# COEX_PDB_schematics.net
KiCad netlist of a schematic drawn in Altium Designer
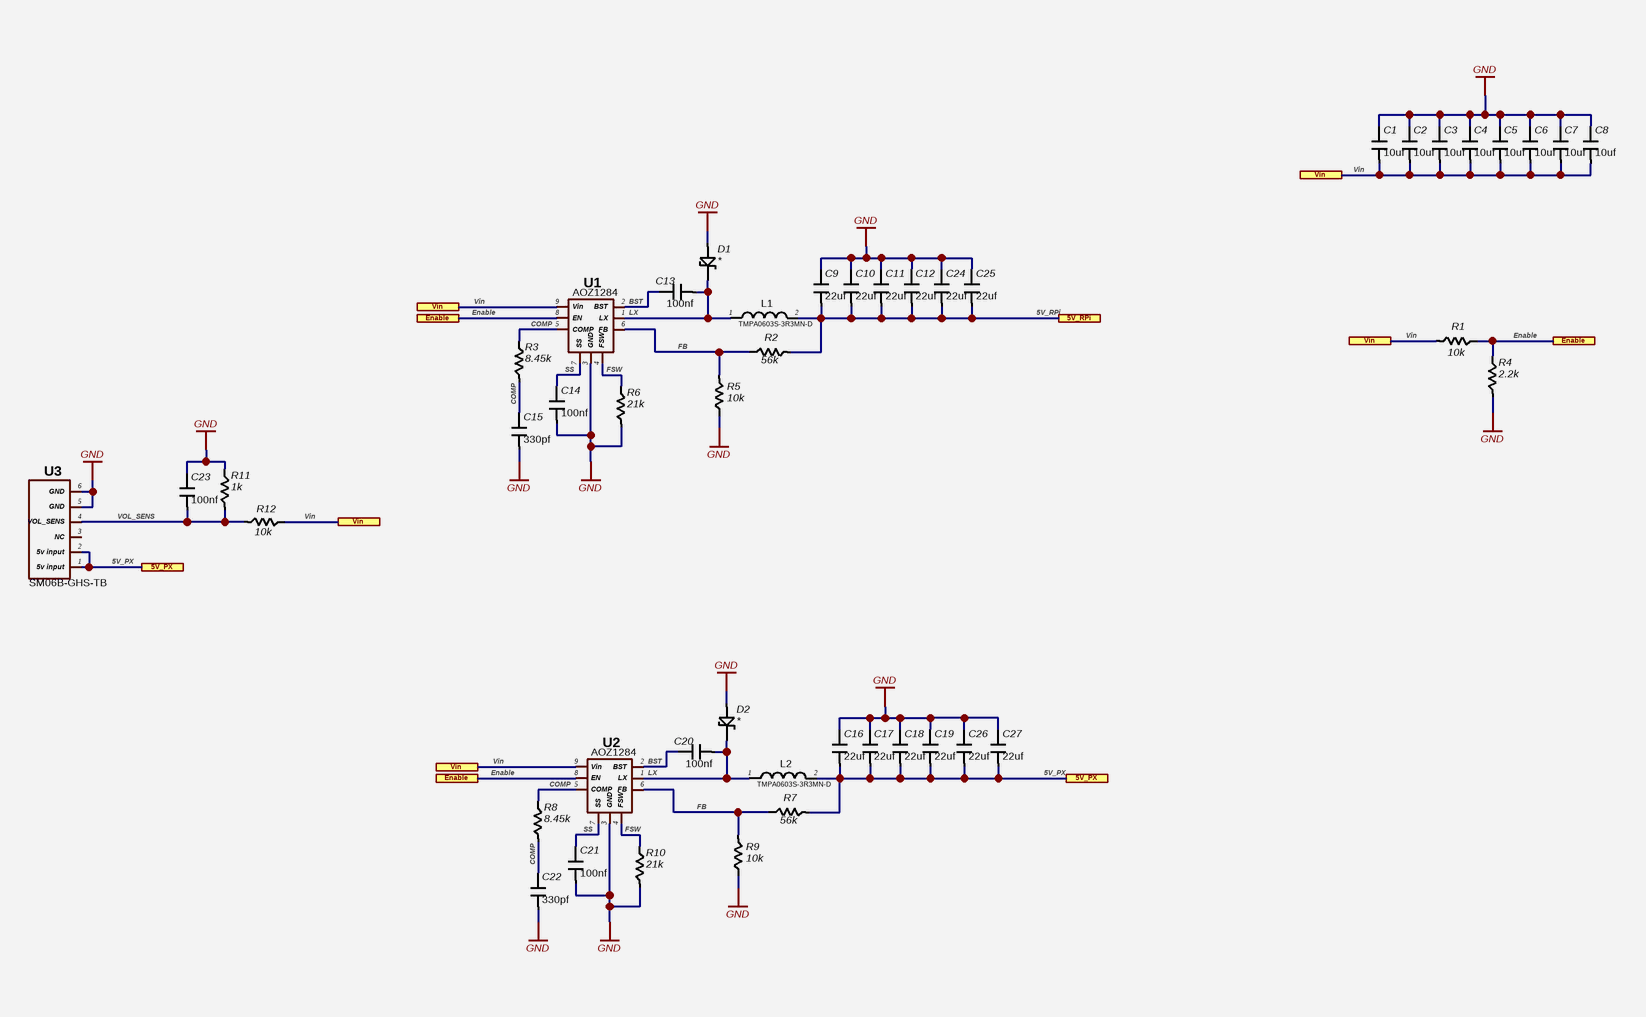
[diagram p0: COEX PDB schematics.SchDoc]

(export (version "E")
  (design (tool "Eeschema 10.0.6"))
  (components
    (comp (ref "C1")
      (value "10uf")
      (footprint "Capasitor 0805")
      (description "Multilayer Ceramic Capacitors MLCC - SMD/SMT 10uF 35V 0805")
      (fields
        (field (name "PART NUMBER") "GRM21BR6YA106KE43L")
        (field (name "MANUFACTURER") "Murata Electronics")
      )
      (libsource (lib "Schematic symbols library") (part "Capacitor MLCC"))
    )
    (comp (ref "C2")
      (value "10uf")
      (footprint "Capasitor 0805")
      (description "Multilayer Ceramic Capacitors MLCC - SMD/SMT 10uF 35V 0805")
      (fields
        (field (name "PART NUMBER") "GRM21BR6YA106KE43L")
        (field (name "MANUFACTURER") "Murata Electronics")
      )
      (libsource (lib "Schematic symbols library") (part "Capacitor MLCC"))
    )
    (comp (ref "C3")
      (value "10uf")
      (footprint "Capasitor 0805")
      (description "Multilayer Ceramic Capacitors MLCC - SMD/SMT 10uF 35V 0805")
      (fields
        (field (name "PART NUMBER") "GRM21BR6YA106KE43L")
        (field (name "MANUFACTURER") "Murata Electronics")
      )
      (libsource (lib "Schematic symbols library") (part "Capacitor MLCC"))
    )
    (comp (ref "C4")
      (value "10uf")
      (footprint "Capasitor 0805")
      (description "Multilayer Ceramic Capacitors MLCC - SMD/SMT 10uF 35V 0805")
      (fields
        (field (name "PART NUMBER") "GRM21BR6YA106KE43L")
        (field (name "MANUFACTURER") "Murata Electronics")
      )
      (libsource (lib "") (part "Capacitor MLCC_1"))
    )
    (comp (ref "C5")
      (value "10uf")
      (footprint "Capasitor 0805")
      (description "Multilayer Ceramic Capacitors MLCC - SMD/SMT 10uF 35V 0805")
      (fields
        (field (name "PART NUMBER") "GRM21BR6YA106KE43L")
        (field (name "MANUFACTURER") "Murata Electronics")
      )
      (libsource (lib "Schematic symbols library") (part "Capacitor MLCC"))
    )
    (comp (ref "C6")
      (value "10uf")
      (footprint "Capasitor 0805")
      (description "Multilayer Ceramic Capacitors MLCC - SMD/SMT 10uF 35V 0805")
      (fields
        (field (name "PART NUMBER") "GRM21BR6YA106KE43L")
        (field (name "MANUFACTURER") "Murata Electronics")
      )
      (libsource (lib "Schematic symbols library") (part "Capacitor MLCC"))
    )
    (comp (ref "C7")
      (value "10uf")
      (footprint "Capasitor 0805")
      (description "Multilayer Ceramic Capacitors MLCC - SMD/SMT 10uF 35V 0805")
      (fields
        (field (name "PART NUMBER") "GRM21BR6YA106KE43L")
        (field (name "MANUFACTURER") "Murata Electronics")
      )
      (libsource (lib "Schematic symbols library") (part "Capacitor MLCC"))
    )
    (comp (ref "C8")
      (value "10uf")
      (footprint "Capasitor 0805")
      (description "Multilayer Ceramic Capacitors MLCC - SMD/SMT 10uF 35V 0805")
      (fields
        (field (name "PART NUMBER") "GRM21BR6YA106KE43L")
        (field (name "MANUFACTURER") "Murata Electronics")
      )
      (libsource (lib "Schematic symbols library") (part "Capacitor MLCC"))
    )
    (comp (ref "C9")
      (value "22uf")
      (footprint "Capasitor 0603")
      (description "Multilayer Ceramic Capacitors MLCC - SMD/SMT 22uF 10V 0603")
      (fields
        (field (name "PART NUMBER") "CL10A226MP8NUNE")
        (field (name "MANUFACTURER") "Samsung Electro-Mechanics")
      )
      (libsource (lib "Schematic symbols library") (part "Capacitor MLCC"))
    )
    (comp (ref "C10")
      (value "22uf")
      (footprint "Capasitor 0603")
      (description "Multilayer Ceramic Capacitors MLCC - SMD/SMT 22uF 10V 0603")
      (fields
        (field (name "PART NUMBER") "CL10A226MP8NUNE")
        (field (name "MANUFACTURER") "Samsung Electro-Mechanics")
      )
      (libsource (lib "Schematic symbols library") (part "Capacitor MLCC"))
    )
    (comp (ref "C11")
      (value "22uf")
      (footprint "Capasitor 0603")
      (description "Multilayer Ceramic Capacitors MLCC - SMD/SMT 22uF 10V 0603")
      (fields
        (field (name "PART NUMBER") "CL10A226MP8NUNE")
        (field (name "MANUFACTURER") "Samsung Electro-Mechanics")
      )
      (libsource (lib "Schematic symbols library") (part "Capacitor MLCC"))
    )
    (comp (ref "C12")
      (value "22uf")
      (footprint "Capasitor 0603")
      (description "Multilayer Ceramic Capacitors MLCC - SMD/SMT 22uF 10V 0603")
      (fields
        (field (name "PART NUMBER") "CL10A226MP8NUNE")
        (field (name "MANUFACTURER") "Samsung Electro-Mechanics")
      )
      (libsource (lib "Schematic symbols library") (part "Capacitor MLCC"))
    )
    (comp (ref "C13")
      (value "100nf")
      (footprint "Capasitor 0402")
      (description "Multilayer Ceramic Capacitors MLCC - SMD/SMT 100nF 25V 0402")
      (fields
        (field (name "PART NUMBER") "0402B104J250NT")
        (field (name "MANUFACTURER") "Guangdong Fenghua Advanced Tech")
      )
      (libsource (lib "Schematic symbols library") (part "Capacitor MLCC"))
    )
    (comp (ref "C14")
      (value "100nf")
      (footprint "Capasitor 0402")
      (description "Multilayer Ceramic Capacitors MLCC - SMD/SMT 100nF 25V 0402")
      (fields
        (field (name "PART NUMBER") "0402B104J250NT")
        (field (name "MANUFACTURER") "Guangdong Fenghua Advanced Tech")
      )
      (libsource (lib "Schematic symbols library") (part "Capacitor MLCC"))
    )
    (comp (ref "C15")
      (value "330pf")
      (footprint "Capasitor 0402")
      (description "Multilayer Ceramic Capacitors MLCC - SMD/SMT 330pF 50V 0402")
      (fields (field (name "PART NUMBER") "CC0402JRNPO9BN331") (field (name "MANUFACTURER") "YAGEO"))
      (libsource (lib "Schematic symbols library") (part "Capacitor MLCC"))
    )
    (comp (ref "C16")
      (value "22uf")
      (footprint "Capasitor 0603")
      (description "Multilayer Ceramic Capacitors MLCC - SMD/SMT 22uF 10V 0603")
      (fields
        (field (name "PART NUMBER") "CL10A226MP8NUNE")
        (field (name "MANUFACTURER") "Samsung Electro-Mechanics")
      )
      (libsource (lib "Schematic symbols library") (part "Capacitor MLCC"))
    )
    (comp (ref "C17")
      (value "22uf")
      (footprint "Capasitor 0603")
      (description "Multilayer Ceramic Capacitors MLCC - SMD/SMT 22uF 10V 0603")
      (fields
        (field (name "PART NUMBER") "CL10A226MP8NUNE")
        (field (name "MANUFACTURER") "Samsung Electro-Mechanics")
      )
      (libsource (lib "Schematic symbols library") (part "Capacitor MLCC"))
    )
    (comp (ref "C18")
      (value "22uf")
      (footprint "Capasitor 0603")
      (description "Multilayer Ceramic Capacitors MLCC - SMD/SMT 22uF 10V 0603")
      (fields
        (field (name "PART NUMBER") "CL10A226MP8NUNE")
        (field (name "MANUFACTURER") "Samsung Electro-Mechanics")
      )
      (libsource (lib "Schematic symbols library") (part "Capacitor MLCC"))
    )
    (comp (ref "C19")
      (value "22uf")
      (footprint "Capasitor 0603")
      (description "Multilayer Ceramic Capacitors MLCC - SMD/SMT 22uF 10V 0603")
      (fields
        (field (name "PART NUMBER") "CL10A226MP8NUNE")
        (field (name "MANUFACTURER") "Samsung Electro-Mechanics")
      )
      (libsource (lib "Schematic symbols library") (part "Capacitor MLCC"))
    )
    (comp (ref "C20")
      (value "100nf")
      (footprint "Capasitor 0402")
      (description "Multilayer Ceramic Capacitors MLCC - SMD/SMT 100nF 25V 0402")
      (fields
        (field (name "PART NUMBER") "0402B104J250NT")
        (field (name "MANUFACTURER") "Guangdong Fenghua Advanced Tech")
      )
      (libsource (lib "Schematic symbols library") (part "Capacitor MLCC"))
    )
    (comp (ref "C21")
      (value "100nf")
      (footprint "Capasitor 0402")
      (description "Multilayer Ceramic Capacitors MLCC - SMD/SMT 100nF 25V 0402")
      (fields
        (field (name "PART NUMBER") "0402B104J250NT")
        (field (name "MANUFACTURER") "Guangdong Fenghua Advanced Tech")
      )
      (libsource (lib "Schematic symbols library") (part "Capacitor MLCC"))
    )
    (comp (ref "C22")
      (value "330pf")
      (footprint "Capasitor 0402")
      (description "Multilayer Ceramic Capacitors MLCC - SMD/SMT 330pF 50V 0402")
      (fields (field (name "PART NUMBER") "CC0402JRNPO9BN331") (field (name "MANUFACTURER") "YAGEO"))
      (libsource (lib "Schematic symbols library") (part "Capacitor MLCC"))
    )
    (comp (ref "C23")
      (value "100nf")
      (footprint "Capasitor 0402")
      (description "Multilayer Ceramic Capacitors MLCC - SMD/SMT 100nF 25V 0402")
      (fields
        (field (name "PART NUMBER") "0402B104J250NT")
        (field (name "MANUFACTURER") "Guangdong Fenghua Advanced Tech")
      )
      (libsource (lib "Schematic symbols library") (part "Capacitor MLCC"))
    )
    (comp (ref "C24")
      (value "22uf")
      (footprint "Capasitor 0603")
      (description "Multilayer Ceramic Capacitors MLCC - SMD/SMT 22uF 10V 0603")
      (fields
        (field (name "PART NUMBER") "CL10A226MP8NUNE")
        (field (name "MANUFACTURER") "Samsung Electro-Mechanics")
      )
      (libsource (lib "Schematic symbols library") (part "Capacitor MLCC"))
    )
    (comp (ref "C25")
      (value "22uf")
      (footprint "Capasitor 0603")
      (description "Multilayer Ceramic Capacitors MLCC - SMD/SMT 22uF 10V 0603")
      (fields
        (field (name "PART NUMBER") "CL10A226MP8NUNE")
        (field (name "MANUFACTURER") "Samsung Electro-Mechanics")
      )
      (libsource (lib "Schematic symbols library") (part "Capacitor MLCC"))
    )
    (comp (ref "C26")
      (value "22uf")
      (footprint "Capasitor 0603")
      (description "Multilayer Ceramic Capacitors MLCC - SMD/SMT 22uF 10V 0603")
      (fields
        (field (name "PART NUMBER") "CL10A226MP8NUNE")
        (field (name "MANUFACTURER") "Samsung Electro-Mechanics")
      )
      (libsource (lib "Schematic symbols library") (part "Capacitor MLCC"))
    )
    (comp (ref "C27")
      (value "22uf")
      (footprint "Capasitor 0603")
      (description "Multilayer Ceramic Capacitors MLCC - SMD/SMT 22uF 10V 0603")
      (fields
        (field (name "PART NUMBER") "CL10A226MP8NUNE")
        (field (name "MANUFACTURER") "Samsung Electro-Mechanics")
      )
      (libsource (lib "Schematic symbols library") (part "Capacitor MLCC"))
    )
    (comp (ref "D1")
      (value "*")
      (footprint "SOD-123FL")
      (description "Schottky Barrier Diodes (SBD) SOD-123")
      (fields (field (name "PART NUMBER") "DSK34") (field (name "MANUFACTURER") "Microdiode Electronics"))
      (libsource (lib "Schematic symbols library") (part "Schottky barrier diode"))
    )
    (comp (ref "D2")
      (value "*")
      (footprint "SOD-123FL")
      (description "Schottky Barrier Diodes (SBD) SOD-123")
      (fields (field (name "PART NUMBER") "DSK34") (field (name "MANUFACTURER") "Microdiode Electronics"))
      (libsource (lib "Schematic symbols library") (part "Schottky barrier diode"))
    )
    (comp (ref "L1")
      (value "TMPA0603S-3R3MN-D")
      (footprint "Inductor SMD 7.1x6.6")
      (description "Power Inductors 3.3uH ±20% 6.5A SMD,7.1x6.6x2.8mm")
      (fields (field (name "MANUFACTURER") "TAITEC"))
      (libsource (lib "Schematic symbols library") (part "FB / Inductor"))
    )
    (comp (ref "L2")
      (value "TMPA0603S-3R3MN-D")
      (footprint "Inductor SMD 7.1x6.6")
      (description "Power Inductors 3.3uH ±20% 6.5A SMD,7.1x6.6x2.8mm")
      (fields (field (name "MANUFACTURER") "TAITEC"))
      (libsource (lib "Schematic symbols library") (part "FB / Inductor"))
    )
    (comp (ref "R1")
      (value "10k")
      (footprint "Resistor 0402")
      (description "Chip Resistor - Surface Mount 10KOhms ±1% 1/16W 0402")
      (fields (field (name "PART NUMBER") "RC0402FR-0710KL") (field (name "MANUFACTURER") "YAGEO"))
      (libsource (lib "") (part "Resistor_1"))
    )
    (comp (ref "R2")
      (value "56k")
      (footprint "Resistor 0402")
      (description "Chip Resistor - Surface Mount 56KOhms ±1% 1/16W 0402")
      (fields (field (name "PART NUMBER") "RC0402FR-0756KL") (field (name "MANUFACTURER") "YAGEO"))
      (libsource (lib "Schematic symbols library") (part "Resistor"))
    )
    (comp (ref "R3")
      (value "8.45k")
      (footprint "Resistor 0402")
      (description "Chip Resistor - Surface Mount 8.45KOhms ±1% 1/16W 0402")
      (fields (field (name "PART NUMBER") "0402WGF8451TCE") (field (name "MANUFACTURER") "Uniroyal Elec"))
      (libsource (lib "Schematic symbols library") (part "Resistor"))
    )
    (comp (ref "R4")
      (value "2.2k")
      (footprint "Resistor 0402")
      (description "Chip Resistor - Surface Mount 2.2KOhms ±1% 1/16W 0402")
      (fields (field (name "PART NUMBER") "RC0402FR-072K2L") (field (name "MANUFACTURER") "YAGEO"))
      (libsource (lib "Schematic symbols library") (part "Resistor"))
    )
    (comp (ref "R5")
      (value "10k")
      (footprint "Resistor 0402")
      (description "Chip Resistor - Surface Mount 10KOhms ±1% 1/16W 0402")
      (fields (field (name "PART NUMBER") "RC0402FR-0710KL") (field (name "MANUFACTURER") "YAGEO"))
      (libsource (lib "Schematic symbols library") (part "Resistor"))
    )
    (comp (ref "R6")
      (value "21k")
      (footprint "Resistor 0402")
      (description "Chip Resistor - Surface Mount 21KOhms ±1% 1/16W 0402")
      (fields (field (name "PART NUMBER") "RC0402FR-0721KL") (field (name "MANUFACTURER") "YAGEO"))
      (libsource (lib "Schematic symbols library") (part "Resistor"))
    )
    (comp (ref "R7")
      (value "56k")
      (footprint "Resistor 0402")
      (description "Chip Resistor - Surface Mount 56KOhms ±1% 1/16W 0402")
      (fields (field (name "PART NUMBER") "RC0402FR-0756KL") (field (name "MANUFACTURER") "YAGEO"))
      (libsource (lib "Schematic symbols library") (part "Resistor"))
    )
    (comp (ref "R8")
      (value "8.45k")
      (footprint "Resistor 0402")
      (description "Chip Resistor - Surface Mount 8.45KOhms ±1% 1/16W 0402")
      (fields (field (name "PART NUMBER") "0402WGF8451TCE") (field (name "MANUFACTURER") "Uniroyal Elec"))
      (libsource (lib "Schematic symbols library") (part "Resistor"))
    )
    (comp (ref "R9")
      (value "10k")
      (footprint "Resistor 0402")
      (description "Chip Resistor - Surface Mount 10KOhms ±1% 1/16W 0402")
      (fields (field (name "PART NUMBER") "RC0402FR-0710KL") (field (name "MANUFACTURER") "YAGEO"))
      (libsource (lib "Schematic symbols library") (part "Resistor"))
    )
    (comp (ref "R10")
      (value "21k")
      (footprint "Resistor 0402")
      (description "Chip Resistor - Surface Mount 21KOhms ±1% 1/16W 0402")
      (fields (field (name "PART NUMBER") "RC0402FR-0721KL") (field (name "MANUFACTURER") "YAGEO"))
      (libsource (lib "Schematic symbols library") (part "Resistor"))
    )
    (comp (ref "R11")
      (value "1k")
      (footprint "Resistor 0402")
      (description "Chip Resistor - Surface Mount 1KOhms ±1% 1/16W 0402")
      (fields (field (name "PART NUMBER") "RC0402FR-071KL") (field (name "MANUFACTURER") "YAGEO"))
      (libsource (lib "Schematic symbols library") (part "Resistor"))
    )
    (comp (ref "R12")
      (value "10k")
      (footprint "Resistor 0402")
      (description "Chip Resistor - Surface Mount 10KOhms ±1% 1/16W 0402")
      (fields (field (name "PART NUMBER") "RC0402FR-0710KL") (field (name "MANUFACTURER") "YAGEO"))
      (libsource (lib "Schematic symbols library") (part "Resistor"))
    )
    (comp (ref "U1")
      (value "AOZ1284")
      (footprint "SOIC-8 (Thermal pad)")
      (description "DC-DC Converters Step-Down Adjustable 1 3V 36V 0.8V 30V 4A SOP-8_EP_150mil")
      (fields (field (name "MANUFACTURER") "Alpha and omega"))
      (libsource (lib "Schematic symbols library") (part "AOZ1284"))
    )
    (comp (ref "U2")
      (value "AOZ1284")
      (footprint "SOIC-8 (Thermal pad)")
      (description "DC-DC Converters Step-Down Adjustable 1 3V 36V 0.8V 30V 4A SOP-8_EP_150mil")
      (fields (field (name "MANUFACTURER") "Alpha and omega"))
      (libsource (lib "Schematic symbols library") (part "AOZ1284"))
    )
    (comp (ref "U3")
      (value "SM06B-GHS-TB")
      (footprint "JST-GH 6 PIN")
      (fields (field (name "MANUFACTURER") "JST Sales America"))
      (libsource (lib "Schematic symbols library") (part "JST-GH 6"))
    )
  )
  (nets
    (net (code "1") (name "/5V_PX") (class "Default")
      (node (ref "C16") (pin "2") (pinfunction "2_2") (pintype "passive"))
      (node (ref "C17") (pin "2") (pinfunction "2_2") (pintype "passive"))
      (node (ref "C18") (pin "2") (pinfunction "2_2") (pintype "passive"))
      (node (ref "C19") (pin "2") (pinfunction "2_2") (pintype "passive"))
      (node (ref "C26") (pin "2") (pinfunction "2_2") (pintype "passive"))
      (node (ref "C27") (pin "2") (pinfunction "2_2") (pintype "passive"))
      (node (ref "L2") (pin "2") (pintype "power_in"))
      (node (ref "R7") (pin "2") (pinfunction "2_2") (pintype "passive"))
      (node (ref "U3") (pin "1") (pinfunction "5v_input_1") (pintype "power_in"))
      (node (ref "U3") (pin "2") (pinfunction "5v_input_2") (pintype "power_in"))
    )
    (net (code "2") (name "/5V_RPi") (class "Default")
      (node (ref "C10") (pin "2") (pinfunction "2_2") (pintype "passive"))
      (node (ref "C11") (pin "2") (pinfunction "2_2") (pintype "passive"))
      (node (ref "C12") (pin "2") (pinfunction "2_2") (pintype "passive"))
      (node (ref "C24") (pin "2") (pinfunction "2_2") (pintype "passive"))
      (node (ref "C25") (pin "2") (pinfunction "2_2") (pintype "passive"))
      (node (ref "C9") (pin "2") (pinfunction "2_2") (pintype "passive"))
      (node (ref "L1") (pin "2") (pintype "power_in"))
      (node (ref "R2") (pin "2") (pinfunction "2_2") (pintype "passive"))
    )
    (net (code "3") (name "/BST") (class "Default")
      (node (ref "C13") (pin "1") (pinfunction "1_1") (pintype "passive"))
      (node (ref "C20") (pin "1") (pinfunction "1_1") (pintype "passive"))
      (node (ref "U1") (pin "2") (pinfunction "BST_2") (pintype "power_in"))
      (node (ref "U2") (pin "2") (pinfunction "BST_2") (pintype "power_in"))
    )
    (net (code "4") (name "/COMP") (class "Default")
      (node (ref "C15") (pin "1") (pinfunction "1_1") (pintype "passive"))
      (node (ref "C22") (pin "1") (pinfunction "1_1") (pintype "passive"))
      (node (ref "R3") (pin "1") (pinfunction "1_1") (pintype "passive"))
      (node (ref "R3") (pin "2") (pinfunction "2_2") (pintype "passive"))
      (node (ref "R8") (pin "1") (pinfunction "1_1") (pintype "passive"))
      (node (ref "R8") (pin "2") (pinfunction "2_2") (pintype "passive"))
      (node (ref "U1") (pin "5") (pinfunction "COMP_5") (pintype "power_in"))
      (node (ref "U2") (pin "5") (pinfunction "COMP_5") (pintype "power_in"))
    )
    (net (code "5") (name "/Enable") (class "Default")
      (node (ref "R1") (pin "1") (pinfunction "1_1") (pintype "passive"))
      (node (ref "R4") (pin "1") (pinfunction "1_1") (pintype "passive"))
      (node (ref "U1") (pin "8") (pinfunction "EN_8") (pintype "power_in"))
      (node (ref "U2") (pin "8") (pinfunction "EN_8") (pintype "power_in"))
    )
    (net (code "6") (name "/FB") (class "Default")
      (node (ref "R2") (pin "1") (pinfunction "1_1") (pintype "passive"))
      (node (ref "R5") (pin "2") (pinfunction "2_2") (pintype "passive"))
      (node (ref "R7") (pin "1") (pinfunction "1_1") (pintype "passive"))
      (node (ref "R9") (pin "2") (pinfunction "2_2") (pintype "passive"))
      (node (ref "U1") (pin "6") (pinfunction "FB_6") (pintype "power_in"))
      (node (ref "U2") (pin "6") (pinfunction "FB_6") (pintype "power_in"))
    )
    (net (code "7") (name "/FSW") (class "Default")
      (node (ref "R10") (pin "1") (pinfunction "1_1") (pintype "passive"))
      (node (ref "R6") (pin "1") (pinfunction "1_1") (pintype "passive"))
      (node (ref "U1") (pin "4") (pinfunction "FSW_4") (pintype "power_in"))
      (node (ref "U2") (pin "4") (pinfunction "FSW_4") (pintype "power_in"))
    )
    (net (code "8") (name "/LX") (class "Default")
      (node (ref "C13") (pin "2") (pinfunction "2_2") (pintype "passive"))
      (node (ref "C20") (pin "2") (pinfunction "2_2") (pintype "passive"))
      (node (ref "D1") (pin "1") (pinfunction "1_1") (pintype "passive"))
      (node (ref "D2") (pin "1") (pinfunction "1_1") (pintype "passive"))
      (node (ref "L1") (pin "1") (pintype "power_in"))
      (node (ref "L2") (pin "1") (pintype "power_in"))
      (node (ref "U1") (pin "1") (pinfunction "LX_1") (pintype "power_in"))
      (node (ref "U2") (pin "1") (pinfunction "LX_1") (pintype "power_in"))
    )
    (net (code "9") (name "/SS") (class "Default")
      (node (ref "C14") (pin "1") (pinfunction "1_1") (pintype "passive"))
      (node (ref "C21") (pin "1") (pinfunction "1_1") (pintype "passive"))
      (node (ref "U1") (pin "7") (pinfunction "SS_7") (pintype "power_in"))
      (node (ref "U2") (pin "7") (pinfunction "SS_7") (pintype "power_in"))
    )
    (net (code "10") (name "/VOL_SENS") (class "Default")
      (node (ref "C23") (pin "2") (pinfunction "2_2") (pintype "passive"))
      (node (ref "R11") (pin "2") (pinfunction "2_2") (pintype "passive"))
      (node (ref "R12") (pin "2") (pinfunction "2_2") (pintype "passive"))
      (node (ref "U3") (pin "4") (pinfunction "VOL_SENS_4") (pintype "power_in"))
    )
    (net (code "11") (name "/Vin") (class "Default")
      (node (ref "C1") (pin "2") (pinfunction "2_2") (pintype "passive"))
      (node (ref "C2") (pin "2") (pinfunction "2_2") (pintype "passive"))
      (node (ref "C3") (pin "2") (pinfunction "2_2") (pintype "passive"))
      (node (ref "C4") (pin "2") (pinfunction "2_2") (pintype "passive"))
      (node (ref "C5") (pin "2") (pinfunction "2_2") (pintype "passive"))
      (node (ref "C6") (pin "2") (pinfunction "2_2") (pintype "passive"))
      (node (ref "C7") (pin "2") (pinfunction "2_2") (pintype "passive"))
      (node (ref "C8") (pin "2") (pinfunction "2_2") (pintype "passive"))
      (node (ref "R1") (pin "2") (pinfunction "2_2") (pintype "passive"))
      (node (ref "R12") (pin "1") (pinfunction "1_1") (pintype "passive"))
      (node (ref "U1") (pin "9") (pinfunction "Vin_9") (pintype "power_in"))
      (node (ref "U2") (pin "9") (pinfunction "Vin_9") (pintype "power_in"))
    )
    (net (code "12") (name "GND") (class "Default")
      (node (ref "C1") (pin "1") (pinfunction "1_1") (pintype "passive"))
      (node (ref "C10") (pin "1") (pinfunction "1_1") (pintype "passive"))
      (node (ref "C11") (pin "1") (pinfunction "1_1") (pintype "passive"))
      (node (ref "C12") (pin "1") (pinfunction "1_1") (pintype "passive"))
      (node (ref "C14") (pin "2") (pinfunction "2_2") (pintype "passive"))
      (node (ref "C15") (pin "2") (pinfunction "2_2") (pintype "passive"))
      (node (ref "C16") (pin "1") (pinfunction "1_1") (pintype "passive"))
      (node (ref "C17") (pin "1") (pinfunction "1_1") (pintype "passive"))
      (node (ref "C18") (pin "1") (pinfunction "1_1") (pintype "passive"))
      (node (ref "C19") (pin "1") (pinfunction "1_1") (pintype "passive"))
      (node (ref "C2") (pin "1") (pinfunction "1_1") (pintype "passive"))
      (node (ref "C21") (pin "2") (pinfunction "2_2") (pintype "passive"))
      (node (ref "C22") (pin "2") (pinfunction "2_2") (pintype "passive"))
      (node (ref "C23") (pin "1") (pinfunction "1_1") (pintype "passive"))
      (node (ref "C24") (pin "1") (pinfunction "1_1") (pintype "passive"))
      (node (ref "C25") (pin "1") (pinfunction "1_1") (pintype "passive"))
      (node (ref "C26") (pin "1") (pinfunction "1_1") (pintype "passive"))
      (node (ref "C27") (pin "1") (pinfunction "1_1") (pintype "passive"))
      (node (ref "C3") (pin "1") (pinfunction "1_1") (pintype "passive"))
      (node (ref "C4") (pin "1") (pinfunction "1_1") (pintype "passive"))
      (node (ref "C5") (pin "1") (pinfunction "1_1") (pintype "passive"))
      (node (ref "C6") (pin "1") (pinfunction "1_1") (pintype "passive"))
      (node (ref "C7") (pin "1") (pinfunction "1_1") (pintype "passive"))
      (node (ref "C8") (pin "1") (pinfunction "1_1") (pintype "passive"))
      (node (ref "C9") (pin "1") (pinfunction "1_1") (pintype "passive"))
      (node (ref "D1") (pin "2") (pinfunction "2_2") (pintype "passive"))
      (node (ref "D2") (pin "2") (pinfunction "2_2") (pintype "passive"))
      (node (ref "R10") (pin "2") (pinfunction "2_2") (pintype "passive"))
      (node (ref "R11") (pin "1") (pinfunction "1_1") (pintype "passive"))
      (node (ref "R4") (pin "2") (pinfunction "2_2") (pintype "passive"))
      (node (ref "R5") (pin "1") (pinfunction "1_1") (pintype "passive"))
      (node (ref "R6") (pin "2") (pinfunction "2_2") (pintype "passive"))
      (node (ref "R9") (pin "1") (pinfunction "1_1") (pintype "passive"))
      (node (ref "U1") (pin "3") (pinfunction "GND_3") (pintype "power_in"))
      (node (ref "U2") (pin "3") (pinfunction "GND_3") (pintype "power_in"))
      (node (ref "U3") (pin "5") (pinfunction "GND_5") (pintype "power_in"))
      (node (ref "U3") (pin "6") (pinfunction "GND_6") (pintype "power_in"))
    )
    (net (code "13") (name "unconnected-(U3-NC-Pad3)") (class "Default")
      (node (ref "U3") (pin "3") (pinfunction "NC_3") (pintype "power_in"))
    )
  )
)
